# Serializer_DS90UB913A.net
KiCad netlist of a schematic drawn in Altium Designer
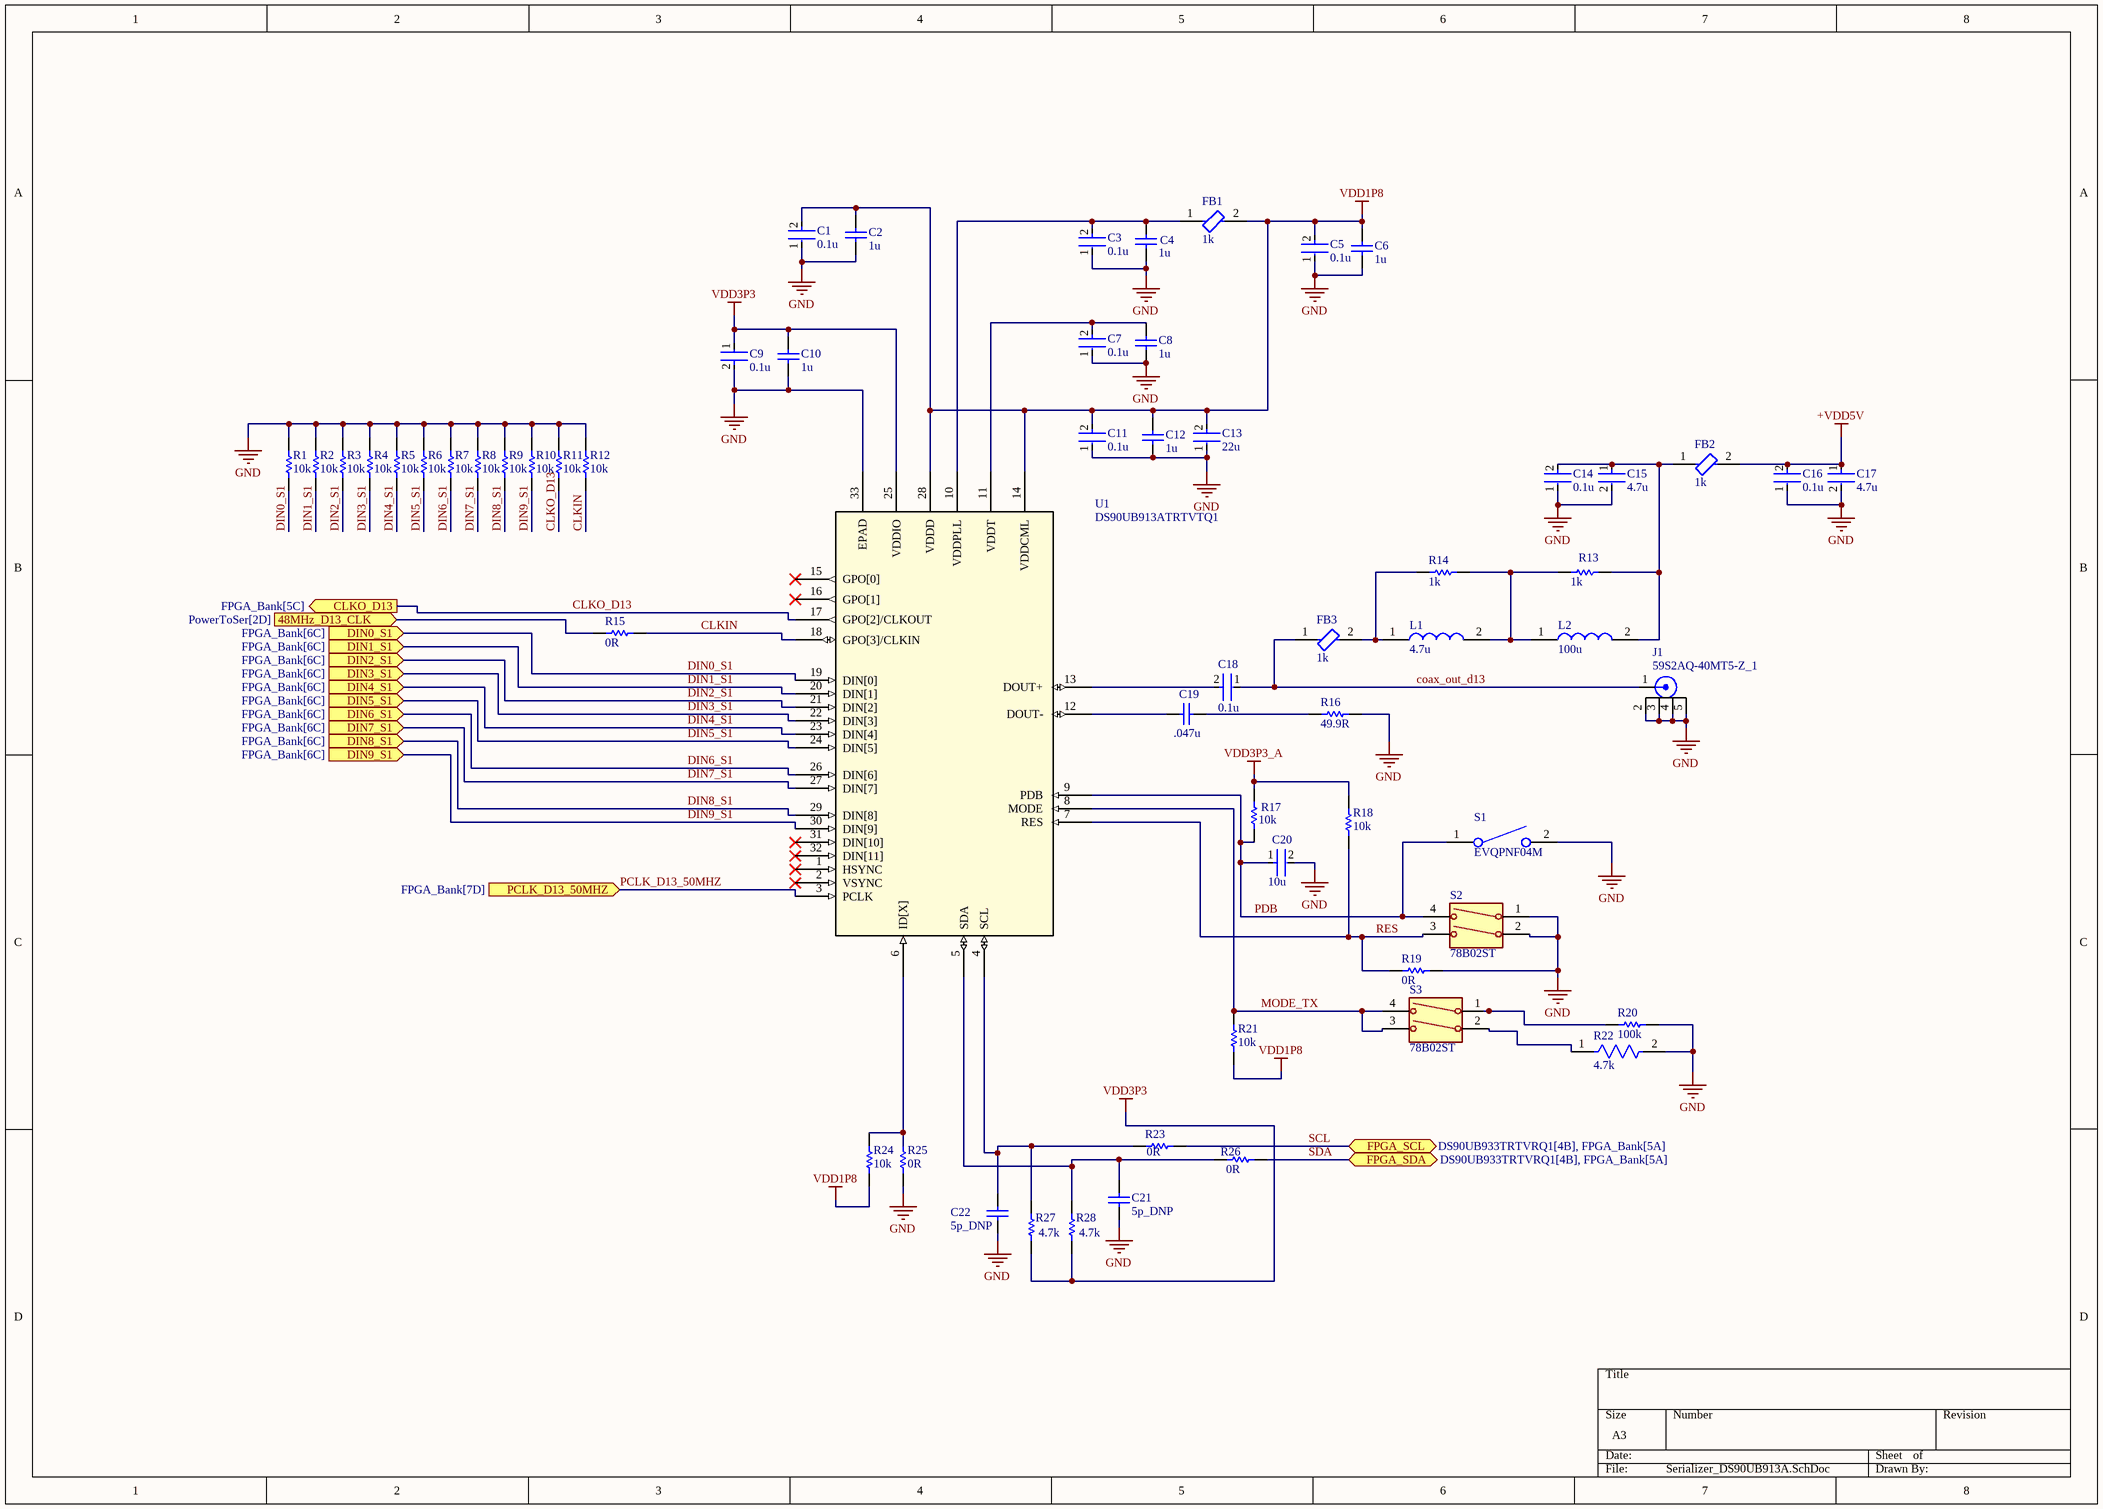
[diagram p0: Serializer_DS90UB913A.SchDoc]

(export (version "E")
  (design (tool "Eeschema 10.0.6"))
  (components
    (comp (ref "C1")
      (value "0.1u")
      (footprint "FP-GRM15-MFG")
      (description "CAP CER 0.1UF 16V X7R 0402")
      (fields (field (name "MANUFACTURER PART NUMBER") "GRM155R71C104KA88D") (field (name "TOLERANCE") "10%"))
      (libsource (lib "Altium Content Vault") (part "236180d848d6139a670b325ea6854c9"))
    )
    (comp (ref "C2")
      (value "1u")
      (footprint "CAPC1608X90X35ML10T15")
      (fields (field (name "MANUFACTURER") "Murata") (field (name "PART NUMBER") "GRM188R71E105KA12D"))
      (libsource (lib "Altium Content Vault") (part "CAP"))
    )
    (comp (ref "C3")
      (value "0.1u")
      (footprint "FP-GRM15-MFG")
      (description "CAP CER 0.1UF 16V X7R 0402")
      (fields (field (name "MANUFACTURER PART NUMBER") "GRM155R71C104KA88D") (field (name "TOLERANCE") "10%"))
      (libsource (lib "Altium Content Vault") (part "236180d848d6139a670b325ea6854c9"))
    )
    (comp (ref "C4")
      (value "1u")
      (footprint "CAPC1608X90X35ML10T15")
      (fields (field (name "MANUFACTURER") "Murata") (field (name "PART NUMBER") "GRM188R71E105KA12D"))
      (libsource (lib "Altium Content Vault") (part "CAP"))
    )
    (comp (ref "C5")
      (value "0.1u")
      (footprint "FP-GRM15-MFG")
      (description "CAP CER 0.1UF 16V X7R 0402")
      (fields (field (name "MANUFACTURER PART NUMBER") "GRM155R71C104KA88D") (field (name "TOLERANCE") "10%"))
      (libsource (lib "Altium Content Vault") (part "236180d848d6139a670b325ea6854c9"))
    )
    (comp (ref "C6")
      (value "1u")
      (footprint "CAPC1608X90X35ML10T15")
      (fields (field (name "MANUFACTURER") "Murata") (field (name "PART NUMBER") "GRM188R71E105KA12D"))
      (libsource (lib "Altium Content Vault") (part "CAP"))
    )
    (comp (ref "C7")
      (value "0.1u")
      (footprint "FP-GRM15-MFG")
      (description "CAP CER 0.1UF 16V X7R 0402")
      (fields (field (name "MANUFACTURER PART NUMBER") "GRM155R71C104KA88D") (field (name "TOLERANCE") "10%"))
      (libsource (lib "Altium Content Vault") (part "236180d848d6139a670b325ea6854c9"))
    )
    (comp (ref "C8")
      (value "1u")
      (footprint "CAPC1608X90X35ML10T15")
      (fields (field (name "MANUFACTURER") "Murata") (field (name "PART NUMBER") "GRM188R71E105KA12D"))
      (libsource (lib "Altium Content Vault") (part "CAP"))
    )
    (comp (ref "C9")
      (value "0.1u")
      (footprint "FP-GRM15-MFG")
      (description "CAP CER 0.1UF 16V X7R 0402")
      (fields (field (name "MANUFACTURER PART NUMBER") "GRM155R71C104KA88D") (field (name "TOLERANCE") "10%"))
      (libsource (lib "Altium Content Vault") (part "236180d848d6139a670b325ea6854c9"))
    )
    (comp (ref "C10")
      (value "1u")
      (footprint "CAPC1608X90X35ML10T15")
      (fields (field (name "MANUFACTURER") "Murata") (field (name "PART NUMBER") "GRM188R71E105KA12D"))
      (libsource (lib "Altium Content Vault") (part "CAP"))
    )
    (comp (ref "C11")
      (value "0.1u")
      (footprint "FP-GRM15-MFG")
      (description "CAP CER 0.1UF 16V X7R 0402")
      (fields (field (name "MANUFACTURER PART NUMBER") "GRM155R71C104KA88D") (field (name "TOLERANCE") "10%"))
      (libsource (lib "Altium Content Vault") (part "236180d848d6139a670b325ea6854c9"))
    )
    (comp (ref "C12")
      (value "1u")
      (footprint "CAPC1608X90X35ML10T15")
      (fields (field (name "MANUFACTURER") "Murata") (field (name "PART NUMBER") "GRM188R71E105KA12D"))
      (libsource (lib "Altium Content Vault") (part "CAP"))
    )
    (comp (ref "C13")
      (value "22u")
      (footprint "FP-GCM32E-0_3-IPC_B")
      (description "Ceramic Capacitor for Automotive 22uF ±10% 16VDC X7R 1210 Embossed T/R")
      (fields (field (name "VOLTAGE") "16V") (field (name "TOLERANCE") "10%"))
      (libsource (lib "Altium Content Vault") (part "f23184f103b6ebe33a8c269c53dcba6"))
    )
    (comp (ref "C14")
      (value "0.1u")
      (footprint "FP-GRM15-MFG")
      (description "CAP CER 0.1UF 16V X7R 0402")
      (fields (field (name "MANUFACTURER PART NUMBER") "GRM155R71C104KA88D") (field (name "TOLERANCE") "10%"))
      (libsource (lib "Altium Content Vault") (part "236180d848d6139a670b325ea6854c9"))
    )
    (comp (ref "C15")
      (value "4.7u")
      (footprint "FP-GRM21B-0_15-MFG")
      (description "CAP CER 4.7UF 16V X7R 0805")
      (fields (field (name "VOLTAGE") "16V") (field (name "TOLERANCE") "10%"))
      (libsource (lib "Altium Content Vault") (part "b4654b650e69147ec39a6b967a45e02"))
    )
    (comp (ref "C16")
      (value "0.1u")
      (footprint "FP-GRM15-MFG")
      (description "CAP CER 0.1UF 16V X7R 0402")
      (fields (field (name "MANUFACTURER PART NUMBER") "GRM155R71C104KA88D") (field (name "TOLERANCE") "10%"))
      (libsource (lib "Altium Content Vault") (part "236180d848d6139a670b325ea6854c9"))
    )
    (comp (ref "C17")
      (value "4.7u")
      (footprint "FP-GRM21B-0_15-MFG")
      (description "CAP CER 4.7UF 16V X7R 0805")
      (fields (field (name "VOLTAGE") "16V") (field (name "TOLERANCE") "10%"))
      (libsource (lib "Altium Content Vault") (part "b4654b650e69147ec39a6b967a45e02"))
    )
    (comp (ref "C18")
      (value "0.1u")
      (footprint "FP-GRM15-MFG")
      (description "CAP CER 0.1UF 16V X7R 0402")
      (fields (field (name "MANUFACTURER PART NUMBER") "GRM155R71C104KA88D") (field (name "TOLERANCE") "10%"))
      (libsource (lib "Altium Content Vault") (part "236180d848d6139a670b325ea6854c9"))
    )
    (comp (ref "C19")
      (value ".047u")
      (footprint "CAPC1608X90X35ML10T15")
      (fields (field (name "MANUFACTURER") "Murata") (field (name "PART NUMBER") "GRM188R71H473KA61D"))
      (libsource (lib "Altium Content Vault") (part "CAP"))
    )
    (comp (ref "C20")
      (value "10u")
      (footprint "FP-GRM21B-0_1-IPC_C")
      (description "Chip Multilayer Ceramic Capacitors for General Purpose, 0805, 10uF, X5R, 15%, 10%, 16V")
      (fields (field (name "TOLERANCE") "10%") (field (name "VOLTAGE") "16V"))
      (libsource (lib "Altium Content Vault") (part "b4654b650e69147ec39a6b967a45e02"))
    )
    (comp (ref "C21")
      (value "5p_DNP")
      (footprint "CAPC1005X55X25LL05T10")
      (fields (field (name "MANUFACTURER") "Murata") (field (name "PART NUMBER") "GRM1555C1H5R0CA01D"))
      (libsource (lib "Altium Content Vault") (part "CAP"))
    )
    (comp (ref "C22")
      (value "5p_DNP")
      (footprint "CAPC1005X55X25LL05T10")
      (fields (field (name "MANUFACTURER") "Murata") (field (name "PART NUMBER") "GRM1555C1H5R0CA01D"))
      (libsource (lib "Altium Content Vault") (part "CAP"))
    )
    (comp (ref "FB1")
      (value "1k")
      (footprint "FP-BLM18-0_15-t0_8-MFG")
      (description "Chip Ferrite Bead, 0603, 1000Ω @ 100MHz, 0.5Ω, 25%, 450mABLM18AG102SN1D")
      (fields (field (name "TOLERANCE") "25%"))
      (libsource (lib "Altium Content Vault") (part "5f30dd21d616792df468990f7003faa"))
    )
    (comp (ref "FB2")
      (value "1k")
      (footprint "FP-BLM18-0_15-t0_8-MFG")
      (description "Chip Ferrite Bead, 0603, 1000Ω @ 100MHz, 0.5Ω, 25%, 450mABLM18AG102SN1D")
      (fields (field (name "TOLERANCE") "25%"))
      (libsource (lib "Altium Content Vault") (part "5f30dd21d616792df468990f7003faa"))
    )
    (comp (ref "FB3")
      (value "1k")
      (footprint "FP-BLM18-0_15-t0_8-MFG")
      (description "Chip Ferrite Bead, 0603, 1000Ω @ 100MHz, 0.5Ω, 25%, 450mABLM18AG102SN1D")
      (fields (field (name "TOLERANCE") "25%"))
      (libsource (lib "Altium Content Vault") (part "5f30dd21d616792df468990f7003faa"))
    )
    (comp (ref "J1")
      (value "59S2AQ-40MT5-Z_1")
      (footprint "SerDes_Eval_Board_Footprints:ROSENBERGER_59S2AQ-40MT5-Z_1")
      (description "RF Connectors / Coaxial Connectors Plug PC-Board SMD Right AngleZWatrBlue")
      (libsource (lib "SerDes_Eval") (part "59S2AQ-40MT5-Z_1"))
    )
    (comp (ref "L1")
      (value "4.7u")
      (footprint "SerDes_Eval_Board_Footprints:1008PS")
      (description "Inductor")
      (fields
        (field (name "MANUFACTURER_PART_NUMBER") "1008PS-472KLB")
        (field (name "MOUSER PART NUMBER") "994-1008PS-472KLB")
      )
      (libsource (lib "SerDes_Eval") (part "1008PS-472KLB"))
    )
    (comp (ref "L2")
      (value "100u")
      (footprint "SerDes_Eval_Board_Footprints:MSS7341T104MLB")
      (description "Inductor")
      (fields
        (field (name "MANUFACTURER_PART_NUMBER") "MSS7341T-104MLD")
        (field (name "MOUSER PART NUMBER") "994-MSS7341T-104MLD")
      )
      (libsource (lib "SerDes_Eval") (part "MSS7341T-104MLB"))
    )
    (comp (ref "R1")
      (value "10k")
      (footprint "RESC1005X40X25ML05T05")
      (fields (field (name "PART NUMBER") "ERJ-2GEJ103X") (field (name "MANUFACTURER") "Panasonic"))
      (libsource (lib "Altium Content Vault") (part "RES"))
    )
    (comp (ref "R2")
      (value "10k")
      (footprint "RESC1005X40X25ML05T05")
      (fields (field (name "PART NUMBER") "ERJ-2GEJ103X") (field (name "MANUFACTURER") "Panasonic"))
      (libsource (lib "Altium Content Vault") (part "RES"))
    )
    (comp (ref "R3")
      (value "10k")
      (footprint "RESC1005X40X25ML05T05")
      (fields (field (name "PART NUMBER") "ERJ-2GEJ103X") (field (name "MANUFACTURER") "Panasonic"))
      (libsource (lib "Altium Content Vault") (part "RES"))
    )
    (comp (ref "R4")
      (value "10k")
      (footprint "RESC1005X40X25ML05T05")
      (fields (field (name "PART NUMBER") "ERJ-2GEJ103X") (field (name "MANUFACTURER") "Panasonic"))
      (libsource (lib "Altium Content Vault") (part "RES"))
    )
    (comp (ref "R5")
      (value "10k")
      (footprint "RESC1005X40X25ML05T05")
      (fields (field (name "PART NUMBER") "ERJ-2GEJ103X") (field (name "MANUFACTURER") "Panasonic"))
      (libsource (lib "Altium Content Vault") (part "RES"))
    )
    (comp (ref "R6")
      (value "10k")
      (footprint "RESC1005X40X25ML05T05")
      (fields (field (name "PART NUMBER") "ERJ-2GEJ103X") (field (name "MANUFACTURER") "Panasonic"))
      (libsource (lib "Altium Content Vault") (part "RES"))
    )
    (comp (ref "R7")
      (value "10k")
      (footprint "RESC1005X40X25ML05T05")
      (fields (field (name "PART NUMBER") "ERJ-2GEJ103X") (field (name "MANUFACTURER") "Panasonic"))
      (libsource (lib "Altium Content Vault") (part "RES"))
    )
    (comp (ref "R8")
      (value "10k")
      (footprint "RESC1005X40X25ML05T05")
      (fields (field (name "PART NUMBER") "ERJ-2GEJ103X") (field (name "MANUFACTURER") "Panasonic"))
      (libsource (lib "Altium Content Vault") (part "RES"))
    )
    (comp (ref "R9")
      (value "10k")
      (footprint "RESC1005X40X25ML05T05")
      (fields (field (name "PART NUMBER") "ERJ-2GEJ103X") (field (name "MANUFACTURER") "Panasonic"))
      (libsource (lib "Altium Content Vault") (part "RES"))
    )
    (comp (ref "R10")
      (value "10k")
      (footprint "RESC1005X40X25ML05T05")
      (fields (field (name "PART NUMBER") "ERJ-2GEJ103X") (field (name "MANUFACTURER") "Panasonic"))
      (libsource (lib "Altium Content Vault") (part "RES"))
    )
    (comp (ref "R11")
      (value "10k")
      (footprint "RESC1005X40X25ML05T05")
      (fields (field (name "PART NUMBER") "ERJ-2GEJ103X") (field (name "MANUFACTURER") "Panasonic"))
      (libsource (lib "Altium Content Vault") (part "RES"))
    )
    (comp (ref "R12")
      (value "10k")
      (footprint "RESC1005X40X25ML05T05")
      (fields (field (name "PART NUMBER") "ERJ-2GEJ103X") (field (name "MANUFACTURER") "Panasonic"))
      (libsource (lib "Altium Content Vault") (part "RES"))
    )
    (comp (ref "R13")
      (value "1k")
      (footprint "RESC1608X55X30LL15T15")
      (fields (field (name "PART NUMBER") "ERJ-3EKF1001V") (field (name "MANUFACTURER") "Panasonic"))
      (libsource (lib "Altium Content Vault") (part "RES"))
    )
    (comp (ref "R14")
      (value "1k")
      (footprint "RESC1608X55X30LL15T15")
      (fields (field (name "PART NUMBER") "ERJ-3EKF1001V") (field (name "MANUFACTURER") "Panasonic"))
      (libsource (lib "Altium Content Vault") (part "RES"))
    )
    (comp (ref "R15")
      (value "0R")
      (footprint "RESC1005X40X25LL05T05")
      (description "Chip Resistor, 0 Ohm, 0.1 W, -55 to 155 degC, 0402 (1005 Metric), RoHS, Tape and Reel")
      (fields (field (name "MANUFACTURER") "Panasonic") (field (name "TOLERANCE") "5%"))
      (libsource (lib "Altium Content Vault") (part "RES-2"))
    )
    (comp (ref "R16")
      (value "49.9R")
      (footprint "RESC1608X55X30ML15T15")
      (fields (field (name "MANUFACTURER") "Panasonic") (field (name "PART NUMBER") "ERJ-3EKF49R9V"))
      (libsource (lib "Altium Content Vault") (part "RES"))
    )
    (comp (ref "R17")
      (value "10k")
      (footprint "RESC1005X40X25ML05T05")
      (fields (field (name "PART NUMBER") "ERJ-2GEJ103X") (field (name "MANUFACTURER") "Panasonic"))
      (libsource (lib "Altium Content Vault") (part "RES"))
    )
    (comp (ref "R18")
      (value "10k")
      (footprint "RESC1005X40X25ML05T05")
      (fields (field (name "PART NUMBER") "ERJ-2GEJ103X") (field (name "MANUFACTURER") "Panasonic"))
      (libsource (lib "Altium Content Vault") (part "RES"))
    )
    (comp (ref "R19")
      (value "0R")
      (footprint "RESC1005X40X25LL05T05")
      (description "Chip Resistor, 0 Ohm, 0.1 W, -55 to 155 degC, 0402 (1005 Metric), RoHS, Tape and Reel")
      (fields (field (name "MANUFACTURER") "Panasonic") (field (name "TOLERANCE") "5%"))
      (libsource (lib "Altium Content Vault") (part "RES-2"))
    )
    (comp (ref "R20")
      (value "100k")
      (footprint "RESC2013X70X40ML20T20")
      (fields (field (name "PART NUMBER") "ERJ-6ENF1003V") (field (name "MANUFACTURER") "Panasonic"))
      (libsource (lib "Altium Content Vault") (part "RES"))
    )
    (comp (ref "R21")
      (value "10k")
      (footprint "RESC1005X40X25ML05T05")
      (fields (field (name "PART NUMBER") "ERJ-2GEJ103X") (field (name "MANUFACTURER") "Panasonic"))
      (libsource (lib "Altium Content Vault") (part "RES"))
    )
    (comp (ref "R22")
      (value "4.7k")
      (footprint "FP-ERJ6GE-MFG")
      (description "RES SMD 4.7K OHM 5% 1/8W 0805")
      (fields (field (name "TOLERANCE") "5%"))
      (libsource (lib "Altium Content Vault") (part "1029c3af85768c4190bb7ad29bc67b5"))
    )
    (comp (ref "R23")
      (value "0R")
      (footprint "RESC1005X40X25LL05T05")
      (description "Chip Resistor, 0 Ohm, 0.1 W, -55 to 155 degC, 0402 (1005 Metric), RoHS, Tape and Reel")
      (fields (field (name "MANUFACTURER") "Panasonic") (field (name "TOLERANCE") "5%"))
      (libsource (lib "Altium Content Vault") (part "RES-2"))
    )
    (comp (ref "R24")
      (value "10k")
      (footprint "RESC1005X40X25ML05T05")
      (fields (field (name "PART NUMBER") "ERJ-2GEJ103X") (field (name "MANUFACTURER") "Panasonic"))
      (libsource (lib "Altium Content Vault") (part "RES"))
    )
    (comp (ref "R25")
      (value "0R")
      (footprint "RESC1005X40X25LL05T05")
      (description "Chip Resistor, 0 Ohm, 0.1 W, -55 to 155 degC, 0402 (1005 Metric), RoHS, Tape and Reel")
      (fields (field (name "MANUFACTURER") "Panasonic") (field (name "TOLERANCE") "5%"))
      (libsource (lib "Altium Content Vault") (part "RES-2"))
    )
    (comp (ref "R26")
      (value "0R")
      (footprint "RESC1005X40X25LL05T05")
      (description "Chip Resistor, 0 Ohm, 0.1 W, -55 to 155 degC, 0402 (1005 Metric), RoHS, Tape and Reel")
      (fields (field (name "MANUFACTURER") "Panasonic") (field (name "TOLERANCE") "5%"))
      (libsource (lib "Altium Content Vault") (part "RES-2"))
    )
    (comp (ref "R27")
      (value "4.7k")
      (footprint "RESC1005X40X25LL05T05")
      (description "Chip Resistor, 4.7 KOhm, +/- 1%, 0.1 W, -55 to 155 degC, 0402 (1005 Metric), RoHS, Tape and Reel")
      (fields (field (name "TOLERANCE") "1%") (field (name "PARTNUMBER") "ERJ-2RKF4701X"))
      (libsource (lib "Altium Content Vault") (part "RES-2"))
    )
    (comp (ref "R28")
      (value "4.7k")
      (footprint "RESC1005X40X25LL05T05")
      (description "Chip Resistor, 4.7 KOhm, +/- 1%, 0.1 W, -55 to 155 degC, 0402 (1005 Metric), RoHS, Tape and Reel")
      (fields (field (name "TOLERANCE") "1%") (field (name "PARTNUMBER") "ERJ-2RKF4701X"))
      (libsource (lib "Altium Content Vault") (part "RES-2"))
    )
    (comp (ref "S1")
      (value "EVQPNF04M")
      (footprint "SamacSys:EVQ5PN05K")
      (description "Switch")
      (libsource (lib "SerDes_Eval") (part "EVQPNF04M"))
    )
    (comp (ref "S2")
      (value "78B02ST")
      (footprint "78B02ST")
      (description "PCB Slide Switch Single Pole Single Throw (SPST) 150 mA Slide")
      (fields (field (name "MOUSER PART NUMBER") "706-78B02ST"))
      (libsource (lib "SerDes_Eval") (part "78B02ST"))
    )
    (comp (ref "S3")
      (value "78B02ST")
      (footprint "78B02ST")
      (description "PCB Slide Switch Single Pole Single Throw (SPST) 150 mA Slide")
      (fields (field (name "MOUSER PART NUMBER") "706-78B02ST"))
      (libsource (lib "SerDes_Eval") (part "78B02ST"))
    )
    (comp (ref "U1")
      (value "DS90UB913ATRTVTQ1")
      (footprint "SerDes_Eval_Board_Footprints:RTV32_3P1X3P1_TEX-L")
      (description "25- to 100-MHz, 10-bit & 12-bit FPD-Link III serializer 32-WQFN -40 to 105")
      (fields (field (name "COPYRIGHT") "Copyright (C) 2025 Ultra Librarian. All rights reserved."))
      (libsource (lib "SerDes_Eval") (part "DS90UB913ATRTVTQ1"))
    )
  )
  (nets
    (net (code "1") (name "+VDD5V") (class "Default")
      (node (ref "C16") (pin "2") (pinfunction "2_2") (pintype "passive"))
      (node (ref "C17") (pin "1") (pinfunction "1_1") (pintype "passive"))
      (node (ref "FB2") (pin "2") (pinfunction "2_2") (pintype "passive"))
    )
    (net (code "2") (name "/48MHz_D13_CLK") (class "Default")
      (node (ref "R15") (pin "2") (pinfunction "2_2") (pintype "passive"))
    )
    (net (code "3") (name "/CLKIN") (class "Default")
      (node (ref "R12") (pin "1") (pinfunction "1_1") (pintype "passive"))
      (node (ref "R15") (pin "1") (pinfunction "1_1") (pintype "passive"))
      (node (ref "U1") (pin "18") (pinfunction "GPO[3]/CLKIN_18") (pintype "bidirectional"))
    )
    (net (code "4") (name "/CLKO_D13") (class "Default")
      (node (ref "R11") (pin "1") (pinfunction "1_1") (pintype "passive"))
      (node (ref "U1") (pin "17") (pinfunction "GPO[2]/CLKOUT_17") (pintype "output"))
    )
    (net (code "5") (name "/DIN0_S1") (class "Default")
      (node (ref "R1") (pin "1") (pinfunction "1_1") (pintype "passive"))
      (node (ref "U1") (pin "19") (pinfunction "DIN[0]_19") (pintype "input"))
    )
    (net (code "6") (name "/DIN1_S1") (class "Default")
      (node (ref "R2") (pin "1") (pinfunction "1_1") (pintype "passive"))
      (node (ref "U1") (pin "20") (pinfunction "DIN[1]_20") (pintype "input"))
    )
    (net (code "7") (name "/DIN2_S1") (class "Default")
      (node (ref "R3") (pin "1") (pinfunction "1_1") (pintype "passive"))
      (node (ref "U1") (pin "21") (pinfunction "DIN[2]_21") (pintype "input"))
    )
    (net (code "8") (name "/DIN3_S1") (class "Default")
      (node (ref "R4") (pin "1") (pinfunction "1_1") (pintype "passive"))
      (node (ref "U1") (pin "22") (pinfunction "DIN[3]_22") (pintype "input"))
    )
    (net (code "9") (name "/DIN4_S1") (class "Default")
      (node (ref "R5") (pin "1") (pinfunction "1_1") (pintype "passive"))
      (node (ref "U1") (pin "23") (pinfunction "DIN[4]_23") (pintype "input"))
    )
    (net (code "10") (name "/DIN5_S1") (class "Default")
      (node (ref "R6") (pin "1") (pinfunction "1_1") (pintype "passive"))
      (node (ref "U1") (pin "24") (pinfunction "DIN[5]_24") (pintype "input"))
    )
    (net (code "11") (name "/DIN6_S1") (class "Default")
      (node (ref "R7") (pin "1") (pinfunction "1_1") (pintype "passive"))
      (node (ref "U1") (pin "26") (pinfunction "DIN[6]_26") (pintype "input"))
    )
    (net (code "12") (name "/DIN7_S1") (class "Default")
      (node (ref "R8") (pin "1") (pinfunction "1_1") (pintype "passive"))
      (node (ref "U1") (pin "27") (pinfunction "DIN[7]_27") (pintype "input"))
    )
    (net (code "13") (name "/DIN8_S1") (class "Default")
      (node (ref "R9") (pin "1") (pinfunction "1_1") (pintype "passive"))
      (node (ref "U1") (pin "29") (pinfunction "DIN[8]_29") (pintype "input"))
    )
    (net (code "14") (name "/DIN9_S1") (class "Default")
      (node (ref "R10") (pin "1") (pinfunction "1_1") (pintype "passive"))
      (node (ref "U1") (pin "30") (pinfunction "DIN[9]_30") (pintype "input"))
    )
    (net (code "15") (name "/MODE_TX") (class "Default")
      (node (ref "R21") (pin "2") (pinfunction "2_2") (pintype "passive"))
      (node (ref "S3") (pin "3") (pinfunction "COM_2_3") (pintype "passive"))
      (node (ref "S3") (pin "4") (pinfunction "NO_2_4") (pintype "passive"))
      (node (ref "U1") (pin "8") (pinfunction "MODE_8") (pintype "input"))
    )
    (net (code "16") (name "/PCLK_D13_50MHZ") (class "Default")
      (node (ref "U1") (pin "3") (pinfunction "PCLK_3") (pintype "input"))
    )
    (net (code "17") (name "/PDB") (class "Default")
      (node (ref "C20") (pin "1") (pinfunction "1_1") (pintype "passive"))
      (node (ref "R17") (pin "1") (pinfunction "1_1") (pintype "passive"))
      (node (ref "S1") (pin "1") (pinfunction "COM_1") (pintype "passive"))
      (node (ref "S2") (pin "4") (pinfunction "NO_2_4") (pintype "passive"))
      (node (ref "U1") (pin "9") (pinfunction "PDB_9") (pintype "input"))
    )
    (net (code "18") (name "/RES") (class "Default")
      (node (ref "R18") (pin "1") (pinfunction "1_1") (pintype "passive"))
      (node (ref "R19") (pin "2") (pinfunction "2_2") (pintype "passive"))
      (node (ref "S2") (pin "3") (pinfunction "COM_2_3") (pintype "passive"))
      (node (ref "U1") (pin "7") (pinfunction "RES_7") (pintype "input"))
    )
    (net (code "19") (name "/SCL") (class "Default")
      (node (ref "R23") (pin "1") (pinfunction "1_1") (pintype "passive"))
    )
    (net (code "20") (name "/SDA") (class "Default")
      (node (ref "R26") (pin "1") (pinfunction "1_1") (pintype "passive"))
    )
    (net (code "21") (name "/coax_out_d13") (class "Default")
      (node (ref "C18") (pin "1") (pinfunction "1_1") (pintype "passive"))
      (node (ref "FB3") (pin "1") (pinfunction "1_1") (pintype "passive"))
      (node (ref "J1") (pin "1") (pinfunction "1_1") (pintype "passive"))
    )
    (net (code "22") (name "GND") (class "Default")
      (node (ref "C1") (pin "1") (pinfunction "1_1") (pintype "passive"))
      (node (ref "C10") (pin "1") (pinfunction "1_1") (pintype "passive"))
      (node (ref "C11") (pin "1") (pinfunction "1_1") (pintype "passive"))
      (node (ref "C12") (pin "1") (pinfunction "1_1") (pintype "passive"))
      (node (ref "C13") (pin "1") (pinfunction "1_1") (pintype "passive"))
      (node (ref "C14") (pin "1") (pinfunction "1_1") (pintype "passive"))
      (node (ref "C15") (pin "2") (pinfunction "2_2") (pintype "passive"))
      (node (ref "C16") (pin "1") (pinfunction "1_1") (pintype "passive"))
      (node (ref "C17") (pin "2") (pinfunction "2_2") (pintype "passive"))
      (node (ref "C2") (pin "1") (pinfunction "1_1") (pintype "passive"))
      (node (ref "C20") (pin "2") (pinfunction "2_2") (pintype "passive"))
      (node (ref "C21") (pin "1") (pinfunction "1_1") (pintype "passive"))
      (node (ref "C22") (pin "1") (pinfunction "1_1") (pintype "passive"))
      (node (ref "C3") (pin "1") (pinfunction "1_1") (pintype "passive"))
      (node (ref "C4") (pin "1") (pinfunction "1_1") (pintype "passive"))
      (node (ref "C5") (pin "1") (pinfunction "1_1") (pintype "passive"))
      (node (ref "C6") (pin "1") (pinfunction "1_1") (pintype "passive"))
      (node (ref "C7") (pin "1") (pinfunction "1_1") (pintype "passive"))
      (node (ref "C8") (pin "1") (pinfunction "1_1") (pintype "passive"))
      (node (ref "C9") (pin "2") (pinfunction "2_2") (pintype "passive"))
      (node (ref "J1") (pin "2") (pinfunction "2_2") (pintype "passive"))
      (node (ref "J1") (pin "3") (pinfunction "3_3") (pintype "passive"))
      (node (ref "J1") (pin "4") (pinfunction "4_4") (pintype "passive"))
      (node (ref "J1") (pin "5") (pinfunction "5_5") (pintype "passive"))
      (node (ref "R1") (pin "2") (pinfunction "2_2") (pintype "passive"))
      (node (ref "R10") (pin "2") (pinfunction "2_2") (pintype "passive"))
      (node (ref "R11") (pin "2") (pinfunction "2_2") (pintype "passive"))
      (node (ref "R12") (pin "2") (pinfunction "2_2") (pintype "passive"))
      (node (ref "R16") (pin "2") (pinfunction "2_2") (pintype "passive"))
      (node (ref "R19") (pin "1") (pinfunction "1_1") (pintype "passive"))
      (node (ref "R2") (pin "2") (pinfunction "2_2") (pintype "passive"))
      (node (ref "R20") (pin "2") (pinfunction "2_2") (pintype "passive"))
      (node (ref "R22") (pin "2") (pinfunction "2_2") (pintype "passive"))
      (node (ref "R25") (pin "1") (pinfunction "1_1") (pintype "passive"))
      (node (ref "R3") (pin "2") (pinfunction "2_2") (pintype "passive"))
      (node (ref "R4") (pin "2") (pinfunction "2_2") (pintype "passive"))
      (node (ref "R5") (pin "2") (pinfunction "2_2") (pintype "passive"))
      (node (ref "R6") (pin "2") (pinfunction "2_2") (pintype "passive"))
      (node (ref "R7") (pin "2") (pinfunction "2_2") (pintype "passive"))
      (node (ref "R8") (pin "2") (pinfunction "2_2") (pintype "passive"))
      (node (ref "R9") (pin "2") (pinfunction "2_2") (pintype "passive"))
      (node (ref "S1") (pin "2") (pinfunction "NO_2") (pintype "passive"))
      (node (ref "S2") (pin "1") (pinfunction "COM_1_1") (pintype "passive"))
      (node (ref "S2") (pin "2") (pinfunction "NO_1_2") (pintype "passive"))
      (node (ref "U1") (pin "33") (pinfunction "EPAD_33") (pintype "passive"))
    )
    (net (code "23") (name "Net-(C14-Pad2)") (class "Default")
      (node (ref "C14") (pin "2") (pinfunction "2_2") (pintype "passive"))
      (node (ref "C15") (pin "1") (pinfunction "1_1") (pintype "passive"))
      (node (ref "FB2") (pin "1") (pinfunction "1_1") (pintype "passive"))
      (node (ref "L2") (pin "2") (pinfunction "2_2") (pintype "passive"))
      (node (ref "R13") (pin "2") (pinfunction "2_2") (pintype "passive"))
    )
    (net (code "24") (name "Net-(C19-Pad2)") (class "Default")
      (node (ref "C19") (pin "2") (pinfunction "2_2") (pintype "passive"))
      (node (ref "R16") (pin "1") (pinfunction "1_1") (pintype "passive"))
    )
    (net (code "25") (name "Net-(FB3-Pad2)") (class "Default")
      (node (ref "FB3") (pin "2") (pinfunction "2_2") (pintype "passive"))
      (node (ref "L1") (pin "1") (pinfunction "1_1") (pintype "passive"))
      (node (ref "R14") (pin "1") (pinfunction "1_1") (pintype "passive"))
    )
    (net (code "26") (name "Net-(L1-Pad2)") (class "Default")
      (node (ref "L1") (pin "2") (pinfunction "2_2") (pintype "passive"))
      (node (ref "L2") (pin "1") (pinfunction "1_1") (pintype "passive"))
      (node (ref "R13") (pin "1") (pinfunction "1_1") (pintype "passive"))
      (node (ref "R14") (pin "2") (pinfunction "2_2") (pintype "passive"))
    )
    (net (code "27") (name "Net-(S3-COM_1)") (class "Default")
      (node (ref "R20") (pin "1") (pinfunction "1_1") (pintype "passive"))
      (node (ref "S3") (pin "1") (pinfunction "COM_1_1") (pintype "passive"))
    )
    (net (code "28") (name "Net-(S3-NO_1)") (class "Default")
      (node (ref "R22") (pin "1") (pinfunction "1_1") (pintype "passive"))
      (node (ref "S3") (pin "2") (pinfunction "NO_1_2") (pintype "passive"))
    )
    (net (code "29") (name "Net-(U1-DOUT+)") (class "Default")
      (node (ref "C18") (pin "2") (pinfunction "2_2") (pintype "passive"))
      (node (ref "U1") (pin "13") (pinfunction "DOUT+_13") (pintype "bidirectional"))
    )
    (net (code "30") (name "Net-(U1-DOUT-)") (class "Default")
      (node (ref "C19") (pin "1") (pinfunction "1_1") (pintype "passive"))
      (node (ref "U1") (pin "12") (pinfunction "DOUT-_12") (pintype "bidirectional"))
    )
    (net (code "31") (name "Net-(U1-ID[X])") (class "Default")
      (node (ref "R24") (pin "2") (pinfunction "2_2") (pintype "passive"))
      (node (ref "R25") (pin "2") (pinfunction "2_2") (pintype "passive"))
      (node (ref "U1") (pin "6") (pinfunction "ID[X]_6") (pintype "input"))
    )
    (net (code "32") (name "Net-(U1-SCL)") (class "Default")
      (node (ref "C22") (pin "2") (pinfunction "2_2") (pintype "passive"))
      (node (ref "R23") (pin "2") (pinfunction "2_2") (pintype "passive"))
      (node (ref "R27") (pin "2") (pinfunction "2_2") (pintype "passive"))
      (node (ref "U1") (pin "4") (pinfunction "SCL_4") (pintype "bidirectional"))
    )
    (net (code "33") (name "Net-(U1-SDA)") (class "Default")
      (node (ref "C21") (pin "2") (pinfunction "2_2") (pintype "passive"))
      (node (ref "R26") (pin "2") (pinfunction "2_2") (pintype "passive"))
      (node (ref "R28") (pin "2") (pinfunction "2_2") (pintype "passive"))
      (node (ref "U1") (pin "5") (pinfunction "SDA_5") (pintype "bidirectional"))
    )
    (net (code "34") (name "Net-(U1-VDDPLL)") (class "Default")
      (node (ref "C3") (pin "2") (pinfunction "2_2") (pintype "passive"))
      (node (ref "C4") (pin "2") (pinfunction "2_2") (pintype "passive"))
      (node (ref "FB1") (pin "1") (pinfunction "1_1") (pintype "passive"))
      (node (ref "U1") (pin "10") (pinfunction "VDDPLL_10") (pintype "power_in"))
    )
    (net (code "35") (name "Net-(U1-VDDT)") (class "Default")
      (node (ref "C7") (pin "2") (pinfunction "2_2") (pintype "passive"))
      (node (ref "C8") (pin "2") (pinfunction "2_2") (pintype "passive"))
      (node (ref "U1") (pin "11") (pinfunction "VDDT_11") (pintype "power_in"))
    )
    (net (code "36") (name "VDD1P8") (class "Default")
      (node (ref "C1") (pin "2") (pinfunction "2_2") (pintype "passive"))
      (node (ref "C11") (pin "2") (pinfunction "2_2") (pintype "passive"))
      (node (ref "C12") (pin "2") (pinfunction "2_2") (pintype "passive"))
      (node (ref "C13") (pin "2") (pinfunction "2_2") (pintype "passive"))
      (node (ref "C2") (pin "2") (pinfunction "2_2") (pintype "passive"))
      (node (ref "C5") (pin "2") (pinfunction "2_2") (pintype "passive"))
      (node (ref "C6") (pin "2") (pinfunction "2_2") (pintype "passive"))
      (node (ref "FB1") (pin "2") (pinfunction "2_2") (pintype "passive"))
      (node (ref "R21") (pin "1") (pinfunction "1_1") (pintype "passive"))
      (node (ref "R24") (pin "1") (pinfunction "1_1") (pintype "passive"))
      (node (ref "U1") (pin "14") (pinfunction "VDDCML_14") (pintype "power_in"))
      (node (ref "U1") (pin "28") (pinfunction "VDDD_28") (pintype "power_in"))
    )
    (net (code "37") (name "VDD3P3") (class "Default")
      (node (ref "C10") (pin "2") (pinfunction "2_2") (pintype "passive"))
      (node (ref "C9") (pin "1") (pinfunction "1_1") (pintype "passive"))
      (node (ref "R27") (pin "1") (pinfunction "1_1") (pintype "passive"))
      (node (ref "R28") (pin "1") (pinfunction "1_1") (pintype "passive"))
      (node (ref "U1") (pin "25") (pinfunction "VDDIO_25") (pintype "power_in"))
    )
    (net (code "38") (name "VDD3P3_A") (class "Default")
      (node (ref "R17") (pin "2") (pinfunction "2_2") (pintype "passive"))
      (node (ref "R18") (pin "2") (pinfunction "2_2") (pintype "passive"))
    )
    (net (code "39") (name "unconnected-(U1-DIN[10]-Pad31)") (class "Default")
      (node (ref "U1") (pin "31") (pinfunction "DIN[10]_31") (pintype "input+no_connect"))
    )
    (net (code "40") (name "unconnected-(U1-DIN[11]-Pad32)") (class "Default")
      (node (ref "U1") (pin "32") (pinfunction "DIN[11]_32") (pintype "input+no_connect"))
    )
    (net (code "41") (name "unconnected-(U1-GPO[0]-Pad15)") (class "Default")
      (node (ref "U1") (pin "15") (pinfunction "GPO[0]_15") (pintype "output+no_connect"))
    )
    (net (code "42") (name "unconnected-(U1-GPO[1]-Pad16)") (class "Default")
      (node (ref "U1") (pin "16") (pinfunction "GPO[1]_16") (pintype "output+no_connect"))
    )
    (net (code "43") (name "unconnected-(U1-HSYNC-Pad1)") (class "Default")
      (node (ref "U1") (pin "1") (pinfunction "HSYNC_1") (pintype "input+no_connect"))
    )
    (net (code "44") (name "unconnected-(U1-VSYNC-Pad2)") (class "Default")
      (node (ref "U1") (pin "2") (pinfunction "VSYNC_2") (pintype "input+no_connect"))
    )
  )
)
